# design.net
KiCad netlist of a schematic drawn in Altium Designer
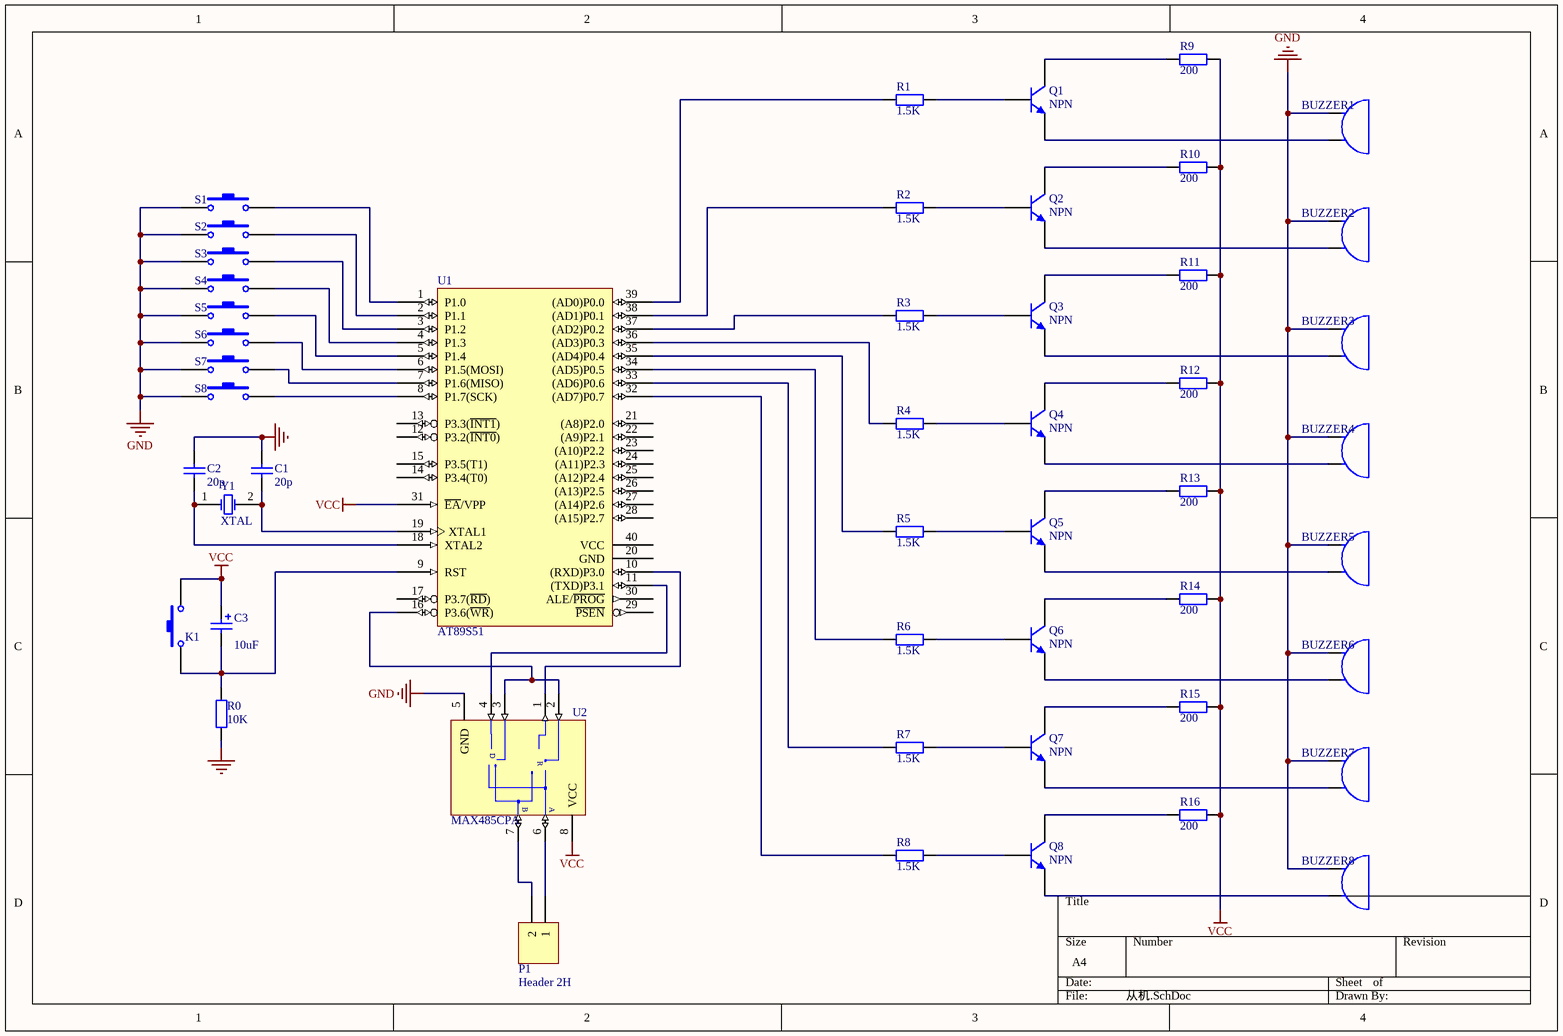
[diagram p0: 从机.SchDoc]

(export (version "E")
  (design (tool "Eeschema 10.0.6"))
  (components
    (comp (ref "BUZZER1") (value "BUZZER") (footprint "SP/10/14") (libsource (lib "原理图封装库") (part "BUZZER")))
    (comp (ref "BUZZER2") (value "BUZZER") (footprint "SP/10/14") (libsource (lib "原理图封装库") (part "BUZZER")))
    (comp (ref "BUZZER3") (value "BUZZER") (footprint "SP/10/14") (libsource (lib "原理图封装库") (part "BUZZER")))
    (comp (ref "BUZZER4") (value "BUZZER") (footprint "SP/10/14") (libsource (lib "原理图封装库") (part "BUZZER")))
    (comp (ref "BUZZER5") (value "BUZZER") (footprint "SP/10/14") (libsource (lib "原理图封装库") (part "BUZZER")))
    (comp (ref "BUZZER6") (value "BUZZER") (footprint "SP/10/14") (libsource (lib "原理图封装库") (part "BUZZER")))
    (comp (ref "BUZZER7") (value "BUZZER") (footprint "SP/10/14") (libsource (lib "原理图封装库") (part "BUZZER")))
    (comp (ref "BUZZER8") (value "BUZZER") (footprint "SP/10/14") (libsource (lib "原理图封装库") (part "BUZZER")))
    (comp (ref "C1")
      (value "20p")
      (footprint "RAD-0.3")
      (description "Capacitor")
      (fields (field (name "Comment") "Cap") (field (name "PUBLISHER") "Altium Limited"))
      (libsource (lib "Miscellaneous Devices") (part "Cap"))
    )
    (comp (ref "C2")
      (value "20p")
      (footprint "RAD-0.3")
      (description "Capacitor")
      (fields (field (name "Comment") "Cap") (field (name "PUBLISHER") "Altium Limited"))
      (libsource (lib "Miscellaneous Devices") (part "Cap"))
    )
    (comp (ref "C3")
      (value "10uF")
      (footprint "POLAR0.8")
      (description "Polarized Capacitor (Axial)")
      (fields (field (name "Comment") "Cap Pol2") (field (name "PUBLISHER") "Altium Limited"))
      (libsource (lib "Miscellaneous Devices") (part "Cap Pol2"))
    )
    (comp (ref "K1")
      (value "SW-PB")
      (footprint "SPST-2")
      (description "Switch")
      (fields (field (name "PUBLISHER") "Altium Limited"))
      (libsource (lib "Miscellaneous Devices") (part "SW-PB"))
    )
    (comp (ref "P1")
      (value "Header 2H")
      (footprint "HDR1X2H")
      (description "Header, 2-Pin, Right Angle")
      (fields (field (name "PUBLISHER") "Altium Limited"))
      (libsource (lib "Miscellaneous Connectors") (part "Header 2H"))
    )
    (comp (ref "Q1")
      (value "NPN")
      (footprint "TO-226")
      (description "NPN Bipolar Transistor")
      (fields (field (name "PUBLISHER") "Altium Limited"))
      (libsource (lib "Miscellaneous Devices") (part "NPN"))
    )
    (comp (ref "Q2")
      (value "NPN")
      (footprint "TO-226")
      (description "NPN Bipolar Transistor")
      (fields (field (name "PUBLISHER") "Altium Limited"))
      (libsource (lib "Miscellaneous Devices") (part "NPN"))
    )
    (comp (ref "Q3")
      (value "NPN")
      (footprint "TO-226")
      (description "NPN Bipolar Transistor")
      (fields (field (name "PUBLISHER") "Altium Limited"))
      (libsource (lib "Miscellaneous Devices") (part "NPN"))
    )
    (comp (ref "Q4")
      (value "NPN")
      (footprint "TO-226")
      (description "NPN Bipolar Transistor")
      (fields (field (name "PUBLISHER") "Altium Limited"))
      (libsource (lib "Miscellaneous Devices") (part "NPN"))
    )
    (comp (ref "Q5")
      (value "NPN")
      (footprint "TO-226")
      (description "NPN Bipolar Transistor")
      (fields (field (name "PUBLISHER") "Altium Limited"))
      (libsource (lib "Miscellaneous Devices") (part "NPN"))
    )
    (comp (ref "Q6")
      (value "NPN")
      (footprint "TO-226")
      (description "NPN Bipolar Transistor")
      (fields (field (name "PUBLISHER") "Altium Limited"))
      (libsource (lib "Miscellaneous Devices") (part "NPN"))
    )
    (comp (ref "Q7")
      (value "NPN")
      (footprint "TO-226")
      (description "NPN Bipolar Transistor")
      (fields (field (name "PUBLISHER") "Altium Limited"))
      (libsource (lib "Miscellaneous Devices") (part "NPN"))
    )
    (comp (ref "Q8")
      (value "NPN")
      (footprint "TO-226")
      (description "NPN Bipolar Transistor")
      (fields (field (name "PUBLISHER") "Altium Limited"))
      (libsource (lib "Miscellaneous Devices") (part "NPN"))
    )
    (comp (ref "R0")
      (value "10K")
      (footprint "AXIAL-0.3")
      (description "Resistor")
      (fields (field (name "PUBLISHER") "Altium Limited"))
      (libsource (lib "") (part "Res2_1"))
    )
    (comp (ref "R1")
      (value "1.5K")
      (footprint "AXIAL-0.3")
      (description "Resistor")
      (fields (field (name "Comment") "10K") (field (name "PUBLISHER") "Altium Limited"))
      (libsource (lib "Miscellaneous Devices") (part "Res2"))
    )
    (comp (ref "R2")
      (value "1.5K")
      (footprint "AXIAL-0.3")
      (description "Resistor")
      (fields (field (name "Comment") "10K") (field (name "PUBLISHER") "Altium Limited"))
      (libsource (lib "Miscellaneous Devices") (part "Res2"))
    )
    (comp (ref "R3")
      (value "1.5K")
      (footprint "AXIAL-0.3")
      (description "Resistor")
      (fields (field (name "Comment") "10K") (field (name "PUBLISHER") "Altium Limited"))
      (libsource (lib "Miscellaneous Devices") (part "Res2"))
    )
    (comp (ref "R4")
      (value "1.5K")
      (footprint "AXIAL-0.3")
      (description "Resistor")
      (fields (field (name "Comment") "10K") (field (name "PUBLISHER") "Altium Limited"))
      (libsource (lib "Miscellaneous Devices") (part "Res2"))
    )
    (comp (ref "R5")
      (value "1.5K")
      (footprint "AXIAL-0.3")
      (description "Resistor")
      (fields (field (name "Comment") "10K") (field (name "PUBLISHER") "Altium Limited"))
      (libsource (lib "Miscellaneous Devices") (part "Res2"))
    )
    (comp (ref "R6")
      (value "1.5K")
      (footprint "AXIAL-0.3")
      (description "Resistor")
      (fields (field (name "Comment") "10K") (field (name "PUBLISHER") "Altium Limited"))
      (libsource (lib "Miscellaneous Devices") (part "Res2"))
    )
    (comp (ref "R7")
      (value "1.5K")
      (footprint "AXIAL-0.3")
      (description "Resistor")
      (fields (field (name "Comment") "10K") (field (name "PUBLISHER") "Altium Limited"))
      (libsource (lib "Miscellaneous Devices") (part "Res2"))
    )
    (comp (ref "R8")
      (value "1.5K")
      (footprint "AXIAL-0.3")
      (description "Resistor")
      (fields (field (name "Comment") "10K") (field (name "PUBLISHER") "Altium Limited"))
      (libsource (lib "Miscellaneous Devices") (part "Res2"))
    )
    (comp (ref "R9")
      (value "200")
      (footprint "AXIAL-0.3")
      (description "Resistor")
      (fields (field (name "PUBLISHER") "Altium Limited"))
      (libsource (lib "Miscellaneous Devices") (part "Res2"))
    )
    (comp (ref "R10")
      (value "200")
      (footprint "AXIAL-0.3")
      (description "Resistor")
      (fields (field (name "PUBLISHER") "Altium Limited"))
      (libsource (lib "Miscellaneous Devices") (part "Res2"))
    )
    (comp (ref "R11")
      (value "200")
      (footprint "AXIAL-0.3")
      (description "Resistor")
      (fields (field (name "PUBLISHER") "Altium Limited"))
      (libsource (lib "Miscellaneous Devices") (part "Res2"))
    )
    (comp (ref "R12")
      (value "200")
      (footprint "AXIAL-0.3")
      (description "Resistor")
      (fields (field (name "PUBLISHER") "Altium Limited"))
      (libsource (lib "Miscellaneous Devices") (part "Res2"))
    )
    (comp (ref "R13")
      (value "200")
      (footprint "AXIAL-0.3")
      (description "Resistor")
      (fields (field (name "PUBLISHER") "Altium Limited"))
      (libsource (lib "Miscellaneous Devices") (part "Res2"))
    )
    (comp (ref "R14")
      (value "200")
      (footprint "AXIAL-0.3")
      (description "Resistor")
      (fields (field (name "PUBLISHER") "Altium Limited"))
      (libsource (lib "Miscellaneous Devices") (part "Res2"))
    )
    (comp (ref "R15")
      (value "200")
      (footprint "AXIAL-0.3")
      (description "Resistor")
      (fields (field (name "PUBLISHER") "Altium Limited"))
      (libsource (lib "Miscellaneous Devices") (part "Res2"))
    )
    (comp (ref "R16")
      (value "200")
      (footprint "AXIAL-0.3")
      (description "Resistor")
      (fields (field (name "PUBLISHER") "Altium Limited"))
      (libsource (lib "Miscellaneous Devices") (part "Res2"))
    )
    (comp (ref "S1")
      (value "SW-PB")
      (footprint "SPST-2")
      (description "Switch")
      (fields (field (name "PUBLISHER") "Altium Limited"))
      (libsource (lib "Miscellaneous Devices") (part "SW-PB"))
    )
    (comp (ref "S2")
      (value "SW-PB")
      (footprint "SPST-2")
      (description "Switch")
      (fields (field (name "PUBLISHER") "Altium Limited"))
      (libsource (lib "Miscellaneous Devices") (part "SW-PB"))
    )
    (comp (ref "S3")
      (value "SW-PB")
      (footprint "SPST-2")
      (description "Switch")
      (fields (field (name "PUBLISHER") "Altium Limited"))
      (libsource (lib "Miscellaneous Devices") (part "SW-PB"))
    )
    (comp (ref "S4")
      (value "SW-PB")
      (footprint "SPST-2")
      (description "Switch")
      (fields (field (name "PUBLISHER") "Altium Limited"))
      (libsource (lib "Miscellaneous Devices") (part "SW-PB"))
    )
    (comp (ref "S5")
      (value "SW-PB")
      (footprint "SPST-2")
      (description "Switch")
      (fields (field (name "PUBLISHER") "Altium Limited"))
      (libsource (lib "Miscellaneous Devices") (part "SW-PB"))
    )
    (comp (ref "S6")
      (value "SW-PB")
      (footprint "SPST-2")
      (description "Switch")
      (fields (field (name "PUBLISHER") "Altium Limited"))
      (libsource (lib "Miscellaneous Devices") (part "SW-PB"))
    )
    (comp (ref "S7")
      (value "SW-PB")
      (footprint "SPST-2")
      (description "Switch")
      (fields (field (name "PUBLISHER") "Altium Limited"))
      (libsource (lib "Miscellaneous Devices") (part "SW-PB"))
    )
    (comp (ref "S8")
      (value "SW-PB")
      (footprint "SPST-2")
      (description "Switch")
      (fields (field (name "PUBLISHER") "Altium Limited"))
      (libsource (lib "Miscellaneous Devices") (part "SW-PB"))
    )
    (comp (ref "U1")
      (value "AT89S51")
      (footprint "DIP-40")
      (description "8-Bit Microcontroller with 4K ISP Flash ROM")
      (libsource (lib "Atmel Microcontroller 8051 Architecture") (part "AT89S51"))
    )
    (comp (ref "U2")
      (value "MAX485CPA")
      (footprint "PA8")
      (description "Low-Power, Slew-Rate-Limited RS-485/RS-422 Transceiver")
      (fields (field (name "PUBLISHER") "Altium Limited"))
      (libsource (lib "Maxim Communication Transceiver") (part "MAX485CPA"))
    )
    (comp (ref "Y1")
      (value "XTAL")
      (footprint "R38")
      (description "Crystal Oscillator")
      (fields (field (name "PUBLISHER") "Altium Limited"))
      (libsource (lib "Miscellaneous Devices") (part "XTAL"))
    )
  )
  (nets
    (net (code "1") (name "GND") (class "Default")
      (node (ref "BUZZER1") (pin "1") (pinfunction "1_1") (pintype "passive"))
      (node (ref "BUZZER2") (pin "1") (pinfunction "1_1") (pintype "passive"))
      (node (ref "BUZZER3") (pin "1") (pinfunction "1_1") (pintype "passive"))
      (node (ref "BUZZER4") (pin "1") (pinfunction "1_1") (pintype "passive"))
      (node (ref "BUZZER5") (pin "1") (pinfunction "1_1") (pintype "passive"))
      (node (ref "BUZZER6") (pin "1") (pinfunction "1_1") (pintype "passive"))
      (node (ref "BUZZER7") (pin "1") (pinfunction "1_1") (pintype "passive"))
      (node (ref "BUZZER8") (pin "1") (pinfunction "1_1") (pintype "passive"))
      (node (ref "C1") (pin "1") (pinfunction "1_1") (pintype "passive"))
      (node (ref "C2") (pin "1") (pinfunction "1_1") (pintype "passive"))
      (node (ref "R0") (pin "2") (pinfunction "2_2") (pintype "passive"))
      (node (ref "S1") (pin "1") (pinfunction "1_1") (pintype "passive"))
      (node (ref "S2") (pin "1") (pinfunction "1_1") (pintype "passive"))
      (node (ref "S3") (pin "1") (pinfunction "1_1") (pintype "passive"))
      (node (ref "S4") (pin "1") (pinfunction "1_1") (pintype "passive"))
      (node (ref "S5") (pin "1") (pinfunction "1_1") (pintype "passive"))
      (node (ref "S6") (pin "1") (pinfunction "1_1") (pintype "passive"))
      (node (ref "S7") (pin "1") (pinfunction "1_1") (pintype "passive"))
      (node (ref "S8") (pin "1") (pinfunction "1_1") (pintype "passive"))
      (node (ref "U2") (pin "5") (pinfunction "GND_5") (pintype "power_in"))
    )
    (net (code "2") (name "Net-(Q1-B)") (class "Default")
      (node (ref "Q1") (pin "2") (pinfunction "B_2") (pintype "passive"))
      (node (ref "R1") (pin "2") (pinfunction "2_2") (pintype "passive"))
    )
    (net (code "3") (name "Net-(Q1-C)") (class "Default")
      (node (ref "Q1") (pin "1") (pinfunction "C_1") (pintype "passive"))
      (node (ref "R9") (pin "1") (pinfunction "1_1") (pintype "passive"))
    )
    (net (code "4") (name "Net-(Q1-E)") (class "Default")
      (node (ref "BUZZER1") (pin "2") (pinfunction "2_2") (pintype "passive"))
      (node (ref "Q1") (pin "3") (pinfunction "E_3") (pintype "passive"))
    )
    (net (code "5") (name "Net-(Q2-B)") (class "Default")
      (node (ref "Q2") (pin "2") (pinfunction "B_2") (pintype "passive"))
      (node (ref "R2") (pin "2") (pinfunction "2_2") (pintype "passive"))
    )
    (net (code "6") (name "Net-(Q2-C)") (class "Default")
      (node (ref "Q2") (pin "1") (pinfunction "C_1") (pintype "passive"))
      (node (ref "R10") (pin "1") (pinfunction "1_1") (pintype "passive"))
    )
    (net (code "7") (name "Net-(Q2-E)") (class "Default")
      (node (ref "BUZZER2") (pin "2") (pinfunction "2_2") (pintype "passive"))
      (node (ref "Q2") (pin "3") (pinfunction "E_3") (pintype "passive"))
    )
    (net (code "8") (name "Net-(Q3-B)") (class "Default")
      (node (ref "Q3") (pin "2") (pinfunction "B_2") (pintype "passive"))
      (node (ref "R3") (pin "2") (pinfunction "2_2") (pintype "passive"))
    )
    (net (code "9") (name "Net-(Q3-C)") (class "Default")
      (node (ref "Q3") (pin "1") (pinfunction "C_1") (pintype "passive"))
      (node (ref "R11") (pin "1") (pinfunction "1_1") (pintype "passive"))
    )
    (net (code "10") (name "Net-(Q3-E)") (class "Default")
      (node (ref "BUZZER3") (pin "2") (pinfunction "2_2") (pintype "passive"))
      (node (ref "Q3") (pin "3") (pinfunction "E_3") (pintype "passive"))
    )
    (net (code "11") (name "Net-(Q4-B)") (class "Default")
      (node (ref "Q4") (pin "2") (pinfunction "B_2") (pintype "passive"))
      (node (ref "R4") (pin "2") (pinfunction "2_2") (pintype "passive"))
    )
    (net (code "12") (name "Net-(Q4-C)") (class "Default")
      (node (ref "Q4") (pin "1") (pinfunction "C_1") (pintype "passive"))
      (node (ref "R12") (pin "1") (pinfunction "1_1") (pintype "passive"))
    )
    (net (code "13") (name "Net-(Q4-E)") (class "Default")
      (node (ref "BUZZER4") (pin "2") (pinfunction "2_2") (pintype "passive"))
      (node (ref "Q4") (pin "3") (pinfunction "E_3") (pintype "passive"))
    )
    (net (code "14") (name "Net-(Q5-B)") (class "Default")
      (node (ref "Q5") (pin "2") (pinfunction "B_2") (pintype "passive"))
      (node (ref "R5") (pin "2") (pinfunction "2_2") (pintype "passive"))
    )
    (net (code "15") (name "Net-(Q5-C)") (class "Default")
      (node (ref "Q5") (pin "1") (pinfunction "C_1") (pintype "passive"))
      (node (ref "R13") (pin "1") (pinfunction "1_1") (pintype "passive"))
    )
    (net (code "16") (name "Net-(Q5-E)") (class "Default")
      (node (ref "BUZZER5") (pin "2") (pinfunction "2_2") (pintype "passive"))
      (node (ref "Q5") (pin "3") (pinfunction "E_3") (pintype "passive"))
    )
    (net (code "17") (name "Net-(Q6-B)") (class "Default")
      (node (ref "Q6") (pin "2") (pinfunction "B_2") (pintype "passive"))
      (node (ref "R6") (pin "2") (pinfunction "2_2") (pintype "passive"))
    )
    (net (code "18") (name "Net-(Q6-C)") (class "Default")
      (node (ref "Q6") (pin "1") (pinfunction "C_1") (pintype "passive"))
      (node (ref "R14") (pin "1") (pinfunction "1_1") (pintype "passive"))
    )
    (net (code "19") (name "Net-(Q6-E)") (class "Default")
      (node (ref "BUZZER6") (pin "2") (pinfunction "2_2") (pintype "passive"))
      (node (ref "Q6") (pin "3") (pinfunction "E_3") (pintype "passive"))
    )
    (net (code "20") (name "Net-(Q7-B)") (class "Default")
      (node (ref "Q7") (pin "2") (pinfunction "B_2") (pintype "passive"))
      (node (ref "R7") (pin "2") (pinfunction "2_2") (pintype "passive"))
    )
    (net (code "21") (name "Net-(Q7-C)") (class "Default")
      (node (ref "Q7") (pin "1") (pinfunction "C_1") (pintype "passive"))
      (node (ref "R15") (pin "1") (pinfunction "1_1") (pintype "passive"))
    )
    (net (code "22") (name "Net-(Q7-E)") (class "Default")
      (node (ref "BUZZER7") (pin "2") (pinfunction "2_2") (pintype "passive"))
      (node (ref "Q7") (pin "3") (pinfunction "E_3") (pintype "passive"))
    )
    (net (code "23") (name "Net-(Q8-B)") (class "Default")
      (node (ref "Q8") (pin "2") (pinfunction "B_2") (pintype "passive"))
      (node (ref "R8") (pin "2") (pinfunction "2_2") (pintype "passive"))
    )
    (net (code "24") (name "Net-(Q8-C)") (class "Default")
      (node (ref "Q8") (pin "1") (pinfunction "C_1") (pintype "passive"))
      (node (ref "R16") (pin "1") (pinfunction "1_1") (pintype "passive"))
    )
    (net (code "25") (name "Net-(Q8-E)") (class "Default")
      (node (ref "BUZZER8") (pin "2") (pinfunction "2_2") (pintype "passive"))
      (node (ref "Q8") (pin "3") (pinfunction "E_3") (pintype "passive"))
    )
    (net (code "26") (name "Net-(U1-(AD0)P0.0)") (class "Default")
      (node (ref "R1") (pin "1") (pinfunction "1_1") (pintype "passive"))
      (node (ref "U1") (pin "39") (pinfunction "(AD0)P0.0_39") (pintype "bidirectional"))
    )
    (net (code "27") (name "Net-(U1-(AD1)P0.1)") (class "Default")
      (node (ref "R2") (pin "1") (pinfunction "1_1") (pintype "passive"))
      (node (ref "U1") (pin "38") (pinfunction "(AD1)P0.1_38") (pintype "bidirectional"))
    )
    (net (code "28") (name "Net-(U1-(AD2)P0.2)") (class "Default")
      (node (ref "R3") (pin "1") (pinfunction "1_1") (pintype "passive"))
      (node (ref "U1") (pin "37") (pinfunction "(AD2)P0.2_37") (pintype "bidirectional"))
    )
    (net (code "29") (name "Net-(U1-(AD3)P0.3)") (class "Default")
      (node (ref "R4") (pin "1") (pinfunction "1_1") (pintype "passive"))
      (node (ref "U1") (pin "36") (pinfunction "(AD3)P0.3_36") (pintype "bidirectional"))
    )
    (net (code "30") (name "Net-(U1-(AD4)P0.4)") (class "Default")
      (node (ref "R5") (pin "1") (pinfunction "1_1") (pintype "passive"))
      (node (ref "U1") (pin "35") (pinfunction "(AD4)P0.4_35") (pintype "bidirectional"))
    )
    (net (code "31") (name "Net-(U1-(AD5)P0.5)") (class "Default")
      (node (ref "R6") (pin "1") (pinfunction "1_1") (pintype "passive"))
      (node (ref "U1") (pin "34") (pinfunction "(AD5)P0.5_34") (pintype "bidirectional"))
    )
    (net (code "32") (name "Net-(U1-(AD6)P0.6)") (class "Default")
      (node (ref "R7") (pin "1") (pinfunction "1_1") (pintype "passive"))
      (node (ref "U1") (pin "33") (pinfunction "(AD6)P0.6_33") (pintype "bidirectional"))
    )
    (net (code "33") (name "Net-(U1-(AD7)P0.7)") (class "Default")
      (node (ref "R8") (pin "1") (pinfunction "1_1") (pintype "passive"))
      (node (ref "U1") (pin "32") (pinfunction "(AD7)P0.7_32") (pintype "bidirectional"))
    )
    (net (code "34") (name "Net-(U1-(RXD)P3.0)") (class "Default")
      (node (ref "U1") (pin "10") (pinfunction "(RXD)P3.0_10") (pintype "bidirectional"))
      (node (ref "U2") (pin "1") (pinfunction "RO_1") (pintype "output"))
    )
    (net (code "35") (name "Net-(U1-(TXD)P3.1)") (class "Default")
      (node (ref "U1") (pin "11") (pinfunction "(TXD)P3.1_11") (pintype "bidirectional"))
      (node (ref "U2") (pin "4") (pinfunction "DI_4") (pintype "input"))
    )
    (net (code "36") (name "Net-(U1-P1.0)") (class "Default")
      (node (ref "S1") (pin "2") (pinfunction "2_2") (pintype "passive"))
      (node (ref "U1") (pin "1") (pinfunction "P1.0_1") (pintype "bidirectional"))
    )
    (net (code "37") (name "Net-(U1-P1.1)") (class "Default")
      (node (ref "S2") (pin "2") (pinfunction "2_2") (pintype "passive"))
      (node (ref "U1") (pin "2") (pinfunction "P1.1_2") (pintype "bidirectional"))
    )
    (net (code "38") (name "Net-(U1-P1.2)") (class "Default")
      (node (ref "S3") (pin "2") (pinfunction "2_2") (pintype "passive"))
      (node (ref "U1") (pin "3") (pinfunction "P1.2_3") (pintype "bidirectional"))
    )
    (net (code "39") (name "Net-(U1-P1.3)") (class "Default")
      (node (ref "S4") (pin "2") (pinfunction "2_2") (pintype "passive"))
      (node (ref "U1") (pin "4") (pinfunction "P1.3_4") (pintype "bidirectional"))
    )
    (net (code "40") (name "Net-(U1-P1.4)") (class "Default")
      (node (ref "S5") (pin "2") (pinfunction "2_2") (pintype "passive"))
      (node (ref "U1") (pin "5") (pinfunction "P1.4_5") (pintype "bidirectional"))
    )
    (net (code "41") (name "Net-(U1-P1.5(MOSI))") (class "Default")
      (node (ref "S6") (pin "2") (pinfunction "2_2") (pintype "passive"))
      (node (ref "U1") (pin "6") (pinfunction "P1.5(MOSI)_6") (pintype "bidirectional"))
    )
    (net (code "42") (name "Net-(U1-P1.6(MISO))") (class "Default")
      (node (ref "S7") (pin "2") (pinfunction "2_2") (pintype "passive"))
      (node (ref "U1") (pin "7") (pinfunction "P1.6(MISO)_7") (pintype "bidirectional"))
    )
    (net (code "43") (name "Net-(U1-P1.7(SCK))") (class "Default")
      (node (ref "S8") (pin "2") (pinfunction "2_2") (pintype "passive"))
      (node (ref "U1") (pin "8") (pinfunction "P1.7(SCK)_8") (pintype "bidirectional"))
    )
    (net (code "44") (name "Net-(U1-P3.6(~{WR}))") (class "Default")
      (node (ref "U1") (pin "16") (pinfunction "P3.6(~{WR})_16") (pintype "bidirectional"))
      (node (ref "U2") (pin "2") (pinfunction "~{RE}_2") (pintype "input"))
      (node (ref "U2") (pin "3") (pinfunction "DE_3") (pintype "input"))
    )
    (net (code "45") (name "Net-(U1-RST)") (class "Default")
      (node (ref "C3") (pin "2") (pinfunction "2_2") (pintype "passive"))
      (node (ref "K1") (pin "1") (pinfunction "1_1") (pintype "passive"))
      (node (ref "R0") (pin "1") (pinfunction "1_1") (pintype "passive"))
      (node (ref "U1") (pin "9") (pinfunction "RST_9") (pintype "input"))
    )
    (net (code "46") (name "Net-(U1-XTAL1)") (class "Default")
      (node (ref "C1") (pin "2") (pinfunction "2_2") (pintype "passive"))
      (node (ref "U1") (pin "19") (pinfunction "XTAL1_19") (pintype "input"))
      (node (ref "Y1") (pin "2") (pinfunction "OSC2_2") (pintype "passive"))
    )
    (net (code "47") (name "Net-(U1-XTAL2)") (class "Default")
      (node (ref "C2") (pin "2") (pinfunction "2_2") (pintype "passive"))
      (node (ref "U1") (pin "18") (pinfunction "XTAL2_18") (pintype "input"))
      (node (ref "Y1") (pin "1") (pinfunction "OSC1_1") (pintype "passive"))
    )
    (net (code "48") (name "Net-(U2-A)") (class "Default")
      (node (ref "P1") (pin "1") (pinfunction "1_1") (pintype "passive"))
      (node (ref "U2") (pin "6") (pinfunction "A_6") (pintype "bidirectional"))
    )
    (net (code "49") (name "Net-(U2-B)") (class "Default")
      (node (ref "P1") (pin "2") (pinfunction "2_2") (pintype "passive"))
      (node (ref "U2") (pin "7") (pinfunction "B_7") (pintype "bidirectional"))
    )
    (net (code "50") (name "VCC") (class "Default")
      (node (ref "C3") (pin "1") (pinfunction "1_1") (pintype "passive"))
      (node (ref "K1") (pin "2") (pinfunction "2_2") (pintype "passive"))
      (node (ref "R10") (pin "2") (pinfunction "2_2") (pintype "passive"))
      (node (ref "R11") (pin "2") (pinfunction "2_2") (pintype "passive"))
      (node (ref "R12") (pin "2") (pinfunction "2_2") (pintype "passive"))
      (node (ref "R13") (pin "2") (pinfunction "2_2") (pintype "passive"))
      (node (ref "R14") (pin "2") (pinfunction "2_2") (pintype "passive"))
      (node (ref "R15") (pin "2") (pinfunction "2_2") (pintype "passive"))
      (node (ref "R16") (pin "2") (pinfunction "2_2") (pintype "passive"))
      (node (ref "R9") (pin "2") (pinfunction "2_2") (pintype "passive"))
      (node (ref "U1") (pin "31") (pinfunction "~{EA}/VPP_31") (pintype "input"))
      (node (ref "U2") (pin "8") (pinfunction "VCC_8") (pintype "power_in"))
    )
    (net (code "51") (name "unconnected-(U1-(A8)P2.0-Pad21)") (class "Default")
      (node (ref "U1") (pin "21") (pinfunction "(A8)P2.0_21") (pintype "bidirectional"))
    )
    (net (code "52") (name "unconnected-(U1-(A9)P2.1-Pad22)") (class "Default")
      (node (ref "U1") (pin "22") (pinfunction "(A9)P2.1_22") (pintype "bidirectional"))
    )
    (net (code "53") (name "unconnected-(U1-(A10)P2.2-Pad23)") (class "Default")
      (node (ref "U1") (pin "23") (pinfunction "(A10)P2.2_23") (pintype "bidirectional"))
    )
    (net (code "54") (name "unconnected-(U1-(A11)P2.3-Pad24)") (class "Default")
      (node (ref "U1") (pin "24") (pinfunction "(A11)P2.3_24") (pintype "bidirectional"))
    )
    (net (code "55") (name "unconnected-(U1-(A12)P2.4-Pad25)") (class "Default")
      (node (ref "U1") (pin "25") (pinfunction "(A12)P2.4_25") (pintype "bidirectional"))
    )
    (net (code "56") (name "unconnected-(U1-(A13)P2.5-Pad26)") (class "Default")
      (node (ref "U1") (pin "26") (pinfunction "(A13)P2.5_26") (pintype "bidirectional"))
    )
    (net (code "57") (name "unconnected-(U1-(A14)P2.6-Pad27)") (class "Default")
      (node (ref "U1") (pin "27") (pinfunction "(A14)P2.6_27") (pintype "bidirectional"))
    )
    (net (code "58") (name "unconnected-(U1-(A15)P2.7-Pad28)") (class "Default")
      (node (ref "U1") (pin "28") (pinfunction "(A15)P2.7_28") (pintype "bidirectional"))
    )
    (net (code "59") (name "unconnected-(U1-ALE{slash}~{PROG}-Pad30)") (class "Default")
      (node (ref "U1") (pin "30") (pinfunction "ALE/~{PROG}_30") (pintype "output"))
    )
    (net (code "60") (name "unconnected-(U1-GND-Pad20)") (class "Default")
      (node (ref "U1") (pin "20") (pinfunction "GND_20") (pintype "power_in"))
    )
    (net (code "61") (name "unconnected-(U1-P3.2(~{INT0})-Pad12)") (class "Default")
      (node (ref "U1") (pin "12") (pinfunction "P3.2(~{INT0})_12") (pintype "bidirectional"))
    )
    (net (code "62") (name "unconnected-(U1-P3.3(~{INT1})-Pad13)") (class "Default")
      (node (ref "U1") (pin "13") (pinfunction "P3.3(~{INT1})_13") (pintype "bidirectional"))
    )
    (net (code "63") (name "unconnected-(U1-P3.4(T0)-Pad14)") (class "Default")
      (node (ref "U1") (pin "14") (pinfunction "P3.4(T0)_14") (pintype "bidirectional"))
    )
    (net (code "64") (name "unconnected-(U1-P3.5(T1)-Pad15)") (class "Default")
      (node (ref "U1") (pin "15") (pinfunction "P3.5(T1)_15") (pintype "bidirectional"))
    )
    (net (code "65") (name "unconnected-(U1-P3.7(~{RD})-Pad17)") (class "Default")
      (node (ref "U1") (pin "17") (pinfunction "P3.7(~{RD})_17") (pintype "bidirectional"))
    )
    (net (code "66") (name "unconnected-(U1-VCC-Pad40)") (class "Default")
      (node (ref "U1") (pin "40") (pinfunction "VCC_40") (pintype "power_in"))
    )
    (net (code "67") (name "unconnected-(U1-~{PSEN}-Pad29)") (class "Default")
      (node (ref "U1") (pin "29") (pinfunction "~{PSEN}_29") (pintype "output"))
    )
  )
)
